# design.net
KiCad netlist of a schematic drawn in Altium Designer
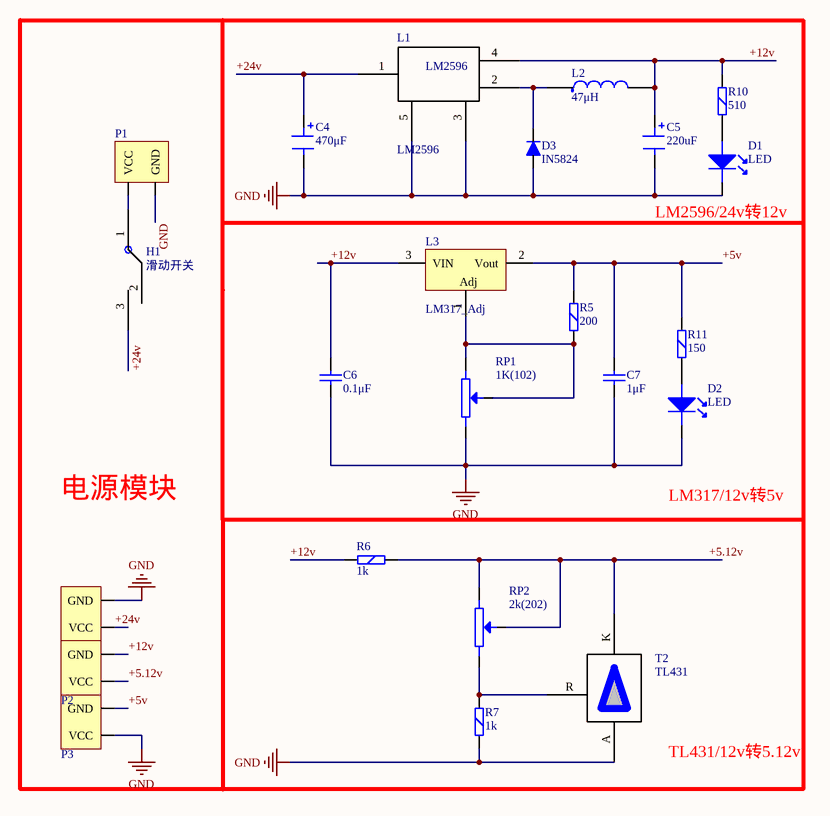
[diagram p0: 电源.SchDoc]

(export (version "E")
  (design (tool "Eeschema 10.0.6"))
  (components
    (comp (ref "C4")
      (value "470μF")
      (footprint "电解电容_大")
      (description "电解电容")
      (libsource (lib "常用直插器件库") (part "电解电容_大"))
    )
    (comp (ref "C5")
      (value "220uF")
      (footprint "电解电容_大")
      (description "电解电容")
      (libsource (lib "常用直插器件库") (part "电解电容_大"))
    )
    (comp (ref "C6")
      (value "0.1μF")
      (footprint "电容_瓷片")
      (description "瓷片电容")
      (libsource (lib "常用直插器件库") (part "电容_瓷片"))
    )
    (comp (ref "C7")
      (value "1μF")
      (footprint "电容_瓷片")
      (description "瓷片电容")
      (libsource (lib "常用直插器件库") (part "电容_瓷片"))
    )
    (comp (ref "D1")
      (value "LED")
      (footprint "LED_G")
      (description "发光二极管")
      (fields (field (name "CREATED") "制造厂商") (field (name "PUBLISHER") "Altium Limited"))
      (libsource (lib "二极管") (part "LED"))
    )
    (comp (ref "D2")
      (value "LED")
      (footprint "LED_G")
      (description "发光二极管")
      (fields (field (name "CREATED") "制造厂商") (field (name "PUBLISHER") "Altium Limited"))
      (libsource (lib "二极管") (part "LED"))
    )
    (comp (ref "D3")
      (value "IN5824")
      (footprint "二极管_整流")
      (description "整流二极管")
      (libsource (lib "常用直插器件库") (part "二极管_整流"))
    )
    (comp (ref "H1") (value "滑动开关") (footprint "滑动开关") (libsource (lib "数控直流电源") (part "滑动开关")))
    (comp (ref "L1") (value "LM2596") (footprint "LM2596") (libsource (lib "数控直流电源") (part "LM2596")))
    (comp (ref "L2")
      (value "47μH")
      (footprint "AL0410_V")
      (fields (field (name "PUBLISHER") "Altium Limited") (field (name "CREATED") "制造厂商"))
      (libsource (lib "电感") (part "Inductor4"))
    )
    (comp (ref "L3")
      (value "LM317_Adj")
      (footprint "7805散热器")
      (description "可调直流稳压芯片")
      (libsource (lib "常用直插器件库") (part "LM317"))
    )
    (comp (ref "P1")
      (value "电源端子2P")
      (footprint "端子 - duplicate")
      (description "电源端子")
      (libsource (lib "常用直插器件库") (part "电源端子2P"))
    )
    (comp (ref "P2")
      (value "电源端子2P")
      (footprint "端子 - duplicate")
      (description "电源端子")
      (libsource (lib "") (part "电源端子2P_1"))
    )
    (comp (ref "P3")
      (value "电源端子2P")
      (footprint "端子 - duplicate")
      (description "电源端子")
      (libsource (lib "") (part "电源端子2P_1"))
    )
    (comp (ref "P4")
      (value "电源端子2P")
      (footprint "端子 - duplicate")
      (description "电源端子")
      (libsource (lib "") (part "电源端子2P_1"))
    )
    (comp (ref "R5")
      (value "200")
      (footprint "1/4WA1")
      (description "1/4W电阻器")
      (fields (field (name "PUBLISHER") "Altium Limited") (field (name "CREATED") "制造厂商"))
      (libsource (lib "电阻") (part "Res_3"))
    )
    (comp (ref "R6")
      (value "1k")
      (footprint "1/4WA1")
      (description "1/4W电阻器")
      (fields (field (name "PUBLISHER") "Altium Limited") (field (name "CREATED") "制造厂商"))
      (libsource (lib "电阻") (part "Res_3"))
    )
    (comp (ref "R7")
      (value "1k")
      (footprint "1/4WA1")
      (description "1/4W电阻器")
      (fields (field (name "PUBLISHER") "Altium Limited") (field (name "CREATED") "制造厂商"))
      (libsource (lib "电阻") (part "Res_3"))
    )
    (comp (ref "R10")
      (value "510")
      (footprint "1/4WA1")
      (description "1/4W电阻器")
      (fields (field (name "PUBLISHER") "Altium Limited") (field (name "CREATED") "制造厂商"))
      (libsource (lib "电阻") (part "Res_3"))
    )
    (comp (ref "R11")
      (value "150")
      (footprint "1/4WA1")
      (description "1/4W电阻器")
      (fields (field (name "PUBLISHER") "Altium Limited") (field (name "CREATED") "制造厂商"))
      (libsource (lib "电阻") (part "Res_3"))
    )
    (comp (ref "RP1")
      (value "1K(102)")
      (footprint "3296-103")
      (description "滑动触点电位器")
      (fields (field (name "PUBLISHER") "Altium Limited") (field (name "CREATED") "制造厂商"))
      (libsource (lib "电阻") (part "RESVR"))
    )
    (comp (ref "RP2")
      (value "2k(202)")
      (footprint "3296-200")
      (description "滑动触点电位器")
      (fields (field (name "PUBLISHER") "Altium Limited") (field (name "CREATED") "制造厂商"))
      (libsource (lib "电阻") (part "RESVR"))
    )
    (comp (ref "T2") (value "TL431") (footprint "TL431") (libsource (lib "数控直流电源") (part "TL431")))
  )
  (nets
    (net (code "1") (name "/+5.12v") (class "Default")
      (node (ref "P2") (pin "1") (pinfunction "VCC_1") (pintype "power_in"))
      (node (ref "R6") (pin "2") (pinfunction "2_2") (pintype "passive"))
      (node (ref "RP2") (pin "1") (pinfunction "1_1") (pintype "passive"))
      (node (ref "RP2") (pin "3") (pinfunction "3_3") (pintype "passive"))
      (node (ref "T2") (pin "K") (pinfunction "K_K") (pintype "passive"))
    )
    (net (code "2") (name "/+5v") (class "Default")
      (node (ref "C7") (pin "2") (pinfunction "2_2") (pintype "passive"))
      (node (ref "L3") (pin "2") (pinfunction "Vout_2") (pintype "passive"))
      (node (ref "P3") (pin "2") (pinfunction "GND_2") (pintype "power_in"))
      (node (ref "R11") (pin "1") (pinfunction "1_1") (pintype "passive"))
      (node (ref "R5") (pin "1") (pinfunction "1_1") (pintype "passive"))
    )
    (net (code "3") (name "/+12v") (class "Default")
      (node (ref "C5") (pin "1") (pinfunction "1_1") (pintype "passive"))
      (node (ref "C6") (pin "2") (pinfunction "2_2") (pintype "passive"))
      (node (ref "L1") (pin "4") (pinfunction "4_4") (pintype "passive"))
      (node (ref "L2") (pin "2") (pinfunction "2_2") (pintype "passive"))
      (node (ref "L3") (pin "3") (pinfunction "VIN_3") (pintype "passive"))
      (node (ref "P2") (pin "2") (pinfunction "GND_2") (pintype "power_in"))
      (node (ref "R10") (pin "1") (pinfunction "1_1") (pintype "passive"))
      (node (ref "R6") (pin "1") (pinfunction "1_1") (pintype "passive"))
    )
    (net (code "4") (name "/+24v") (class "Default")
      (node (ref "C4") (pin "1") (pinfunction "1_1") (pintype "passive"))
      (node (ref "H1") (pin "3") (pinfunction "3_3") (pintype "passive"))
      (node (ref "L1") (pin "1") (pinfunction "1_1") (pintype "passive"))
      (node (ref "P4") (pin "1") (pinfunction "VCC_1") (pintype "power_in"))
    )
    (net (code "5") (name "GND") (class "Default")
      (node (ref "C4") (pin "2") (pinfunction "2_2") (pintype "passive"))
      (node (ref "C5") (pin "2") (pinfunction "2_2") (pintype "passive"))
      (node (ref "C6") (pin "1") (pinfunction "1_1") (pintype "passive"))
      (node (ref "C7") (pin "1") (pinfunction "1_1") (pintype "passive"))
      (node (ref "D1") (pin "2") (pinfunction "K_2") (pintype "passive"))
      (node (ref "D2") (pin "2") (pinfunction "K_2") (pintype "passive"))
      (node (ref "D3") (pin "1") (pinfunction "A_1") (pintype "passive"))
      (node (ref "L1") (pin "3") (pinfunction "3_3") (pintype "passive"))
      (node (ref "L1") (pin "5") (pinfunction "5_5") (pintype "passive"))
      (node (ref "P1") (pin "2") (pinfunction "GND_2") (pintype "power_in"))
      (node (ref "P3") (pin "1") (pinfunction "VCC_1") (pintype "power_in"))
      (node (ref "P4") (pin "2") (pinfunction "GND_2") (pintype "power_in"))
      (node (ref "R7") (pin "2") (pinfunction "2_2") (pintype "passive"))
      (node (ref "RP1") (pin "2") (pinfunction "2_2") (pintype "passive"))
      (node (ref "T2") (pin "A") (pinfunction "A_A") (pintype "passive"))
    )
    (net (code "6") (name "Net-(D1-A)") (class "Default")
      (node (ref "D1") (pin "1") (pinfunction "A_1") (pintype "passive"))
      (node (ref "R10") (pin "2") (pinfunction "2_2") (pintype "passive"))
    )
    (net (code "7") (name "Net-(D2-A)") (class "Default")
      (node (ref "D2") (pin "1") (pinfunction "A_1") (pintype "passive"))
      (node (ref "R11") (pin "2") (pinfunction "2_2") (pintype "passive"))
    )
    (net (code "8") (name "Net-(D3-K)") (class "Default")
      (node (ref "D3") (pin "2") (pinfunction "K_2") (pintype "passive"))
      (node (ref "L1") (pin "2") (pinfunction "2_2") (pintype "passive"))
      (node (ref "L2") (pin "1") (pinfunction "1_1") (pintype "passive"))
    )
    (net (code "9") (name "Net-(L3-Adj)") (class "Default")
      (node (ref "L3") (pin "1") (pinfunction "Adj_1") (pintype "passive"))
      (node (ref "R5") (pin "2") (pinfunction "2_2") (pintype "passive"))
      (node (ref "RP1") (pin "1") (pinfunction "1_1") (pintype "passive"))
      (node (ref "RP1") (pin "3") (pinfunction "3_3") (pintype "passive"))
    )
    (net (code "10") (name "Net-(P1-VCC)") (class "Default")
      (node (ref "H1") (pin "1") (pinfunction "1_1") (pintype "passive"))
      (node (ref "P1") (pin "1") (pinfunction "VCC_1") (pintype "power_in"))
    )
    (net (code "11") (name "Net-(R7-Pad1)") (class "Default")
      (node (ref "R7") (pin "1") (pinfunction "1_1") (pintype "passive"))
      (node (ref "RP2") (pin "2") (pinfunction "2_2") (pintype "passive"))
      (node (ref "T2") (pin "R") (pinfunction "R_R") (pintype "passive"))
    )
    (net (code "12") (name "unconnected-(H1-Pad2)") (class "Default")
      (node (ref "H1") (pin "2") (pinfunction "2_2") (pintype "passive"))
    )
  )
)
